# Main.net
KiCad netlist of a schematic drawn in Altium Designer
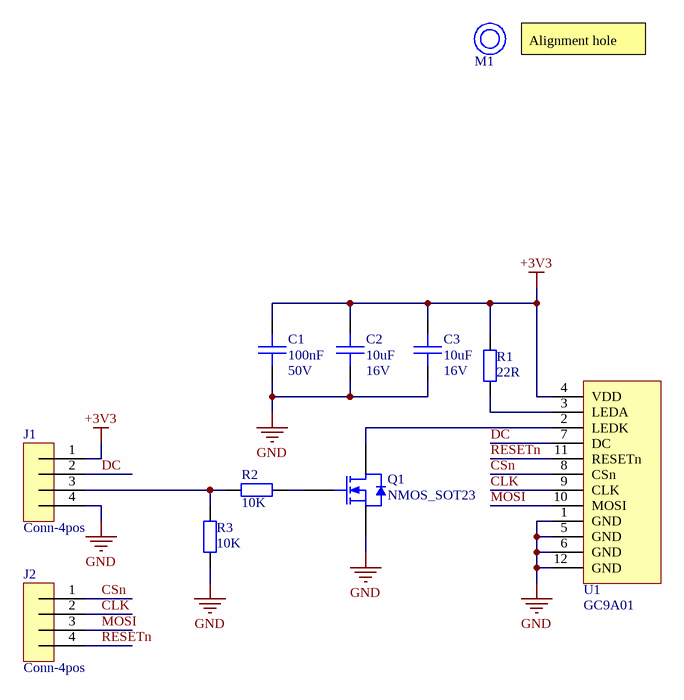
[diagram p0: Main.SchDoc]

(export (version "E")
  (design (tool "Eeschema 10.0.6"))
  (components
    (comp (ref "C1")
      (value "100nF")
      (footprint "C0603")
      (description "General purpose ceramic capacitor")
      (fields
        (field (name "VOLTAGE") "50V")
        (field (name "MANUFACTURER") "TDK Corporation")
        (field (name "MANUFACTURER PART NO") "CGA3E2X7R1H104K080AA")
      )
      (libsource (lib "Moonlight_Library") (part "CAP"))
    )
    (comp (ref "C2")
      (value "10uF")
      (footprint "C0805")
      (description "General purpose ceramic capacitor")
      (fields
        (field (name "VOLTAGE") "16V")
        (field (name "MANUFACTURER") "TDK Corporation")
        (field (name "MANUFACTURER PART NO") "CGA4J1X7S1C106K125AC")
      )
      (libsource (lib "Moonlight_Library") (part "CAP"))
    )
    (comp (ref "C3")
      (value "10uF")
      (footprint "C0805")
      (description "General purpose ceramic capacitor")
      (fields
        (field (name "VOLTAGE") "16V")
        (field (name "MANUFACTURER") "TDK Corporation")
        (field (name "MANUFACTURER PART NO") "CGA4J1X7S1C106K125AC")
      )
      (libsource (lib "Moonlight_Library") (part "CAP"))
    )
    (comp (ref "J1")
      (value "Conn-4pos")
      (footprint "2mm_pads_4")
      (description "2mm pitch solder pads")
      (fields (field (name "MANUFACTURER PART NO") "2mm_pads_4"))
      (libsource (lib "Moonlight_Library") (part "Conn-4pos"))
    )
    (comp (ref "J2")
      (value "Conn-4pos")
      (footprint "2mm_pads_4")
      (description "2mm pitch solder pads")
      (fields (field (name "MANUFACTURER PART NO") "2mm_pads_4"))
      (libsource (lib "Moonlight_Library") (part "Conn-4pos"))
    )
    (comp (ref "M1")
      (value "Mounting_Hole_Unplated")
      (footprint "M1.6_Close_Unplated")
      (description "M1.6 Hole, Unplated")
      (libsource (lib "Moonlight_Library") (part "Mounting_Hole_Unplated"))
    )
    (comp (ref "Q1")
      (value "NMOS_SOT23")
      (footprint "SOT23")
      (description "General purpose N-Channel MOSFET in SOT23 packagge")
      (fields (field (name "MANUFACTURER") "onsemi") (field (name "MANUFACTURER PART NO") "BSS138"))
      (libsource (lib "Moonlight_Library") (part "NMOS_SOT23"))
    )
    (comp (ref "R1")
      (value "22R")
      (footprint "R0603")
      (description "General purpose automotive thick film resistor")
      (fields
        (field (name "MANUFACTURER") "Vishay Dale")
        (field (name "MANUFACTURER PART NO") "CRCW060322R0JNEA")
      )
      (libsource (lib "Moonlight_Library") (part "RES"))
    )
    (comp (ref "R2")
      (value "10K")
      (footprint "R0603")
      (description "General purpose automotive thick film resistor")
      (fields
        (field (name "MANUFACTURER") "Vishay Dale")
        (field (name "MANUFACTURER PART NO") "CRCW060310K0JNEA")
      )
      (libsource (lib "") (part "RES_1"))
    )
    (comp (ref "R3")
      (value "10K")
      (footprint "R0603")
      (description "General purpose automotive thick film resistor")
      (fields
        (field (name "MANUFACTURER") "Vishay Dale")
        (field (name "MANUFACTURER PART NO") "CRCW060310K0JNEA")
      )
      (libsource (lib "Moonlight_Library") (part "RES"))
    )
    (comp (ref "U1")
      (value "GC9A01")
      (footprint "GC9A01")
      (description "240x240 px round IPS display")
      (libsource (lib "Moonlight_Library") (part "GC9A01"))
    )
  )
  (nets
    (net (code "1") (name "+3V3") (class "Default")
      (node (ref "C1") (pin "1") (pinfunction "1_1") (pintype "passive"))
      (node (ref "C2") (pin "1") (pinfunction "1_1") (pintype "passive"))
      (node (ref "C3") (pin "1") (pinfunction "1_1") (pintype "passive"))
      (node (ref "J1") (pin "1") (pinfunction "1_1") (pintype "passive"))
      (node (ref "R1") (pin "2") (pintype "passive"))
      (node (ref "U1") (pin "4") (pinfunction "VDD_4") (pintype "passive"))
    )
    (net (code "2") (name "/CLK") (class "Default")
      (node (ref "J2") (pin "2") (pinfunction "2_2") (pintype "passive"))
      (node (ref "U1") (pin "9") (pinfunction "CLK_9") (pintype "passive"))
    )
    (net (code "3") (name "/CSn") (class "Default")
      (node (ref "J2") (pin "1") (pinfunction "1_1") (pintype "passive"))
      (node (ref "U1") (pin "8") (pinfunction "CSn_8") (pintype "passive"))
    )
    (net (code "4") (name "/DC") (class "Default")
      (node (ref "J1") (pin "2") (pinfunction "2_2") (pintype "passive"))
      (node (ref "U1") (pin "7") (pinfunction "DC_7") (pintype "passive"))
    )
    (net (code "5") (name "/MOSI") (class "Default")
      (node (ref "J2") (pin "3") (pinfunction "3_3") (pintype "passive"))
      (node (ref "U1") (pin "10") (pinfunction "MOSI_10") (pintype "passive"))
    )
    (net (code "6") (name "/RESETn") (class "Default")
      (node (ref "J2") (pin "4") (pinfunction "4_4") (pintype "passive"))
      (node (ref "U1") (pin "11") (pinfunction "RESETn_11") (pintype "passive"))
    )
    (net (code "7") (name "GND") (class "Default")
      (node (ref "C1") (pin "2") (pinfunction "2_2") (pintype "passive"))
      (node (ref "C2") (pin "2") (pinfunction "2_2") (pintype "passive"))
      (node (ref "C3") (pin "2") (pinfunction "2_2") (pintype "passive"))
      (node (ref "J1") (pin "4") (pinfunction "4_4") (pintype "passive"))
      (node (ref "Q1") (pin "2") (pinfunction "S_2") (pintype "passive"))
      (node (ref "R3") (pin "1") (pintype "passive"))
      (node (ref "U1") (pin "1") (pinfunction "GND_1") (pintype "passive"))
      (node (ref "U1") (pin "12") (pinfunction "GND_12") (pintype "passive"))
      (node (ref "U1") (pin "5") (pinfunction "GND_5") (pintype "passive"))
      (node (ref "U1") (pin "6") (pinfunction "GND_6") (pintype "passive"))
    )
    (net (code "8") (name "Net-(J1-Pad3)") (class "Default")
      (node (ref "J1") (pin "3") (pinfunction "3_3") (pintype "passive"))
      (node (ref "R2") (pin "1") (pintype "passive"))
      (node (ref "R3") (pin "2") (pintype "passive"))
    )
    (net (code "9") (name "Net-(Q1-D)") (class "Default")
      (node (ref "Q1") (pin "3") (pinfunction "D_3") (pintype "passive"))
      (node (ref "U1") (pin "2") (pinfunction "LEDK_2") (pintype "passive"))
    )
    (net (code "10") (name "Net-(Q1-G)") (class "Default")
      (node (ref "Q1") (pin "1") (pinfunction "G_1") (pintype "passive"))
      (node (ref "R2") (pin "2") (pintype "passive"))
    )
    (net (code "11") (name "Net-(U1-LEDA)") (class "Default")
      (node (ref "R1") (pin "1") (pintype "passive"))
      (node (ref "U1") (pin "3") (pinfunction "LEDA_3") (pintype "passive"))
    )
  )
)
